# ProProject_TDeck_18650_Charger_2024-02-1.net
KiCad netlist of a schematic drawn in EasyEDA Pro
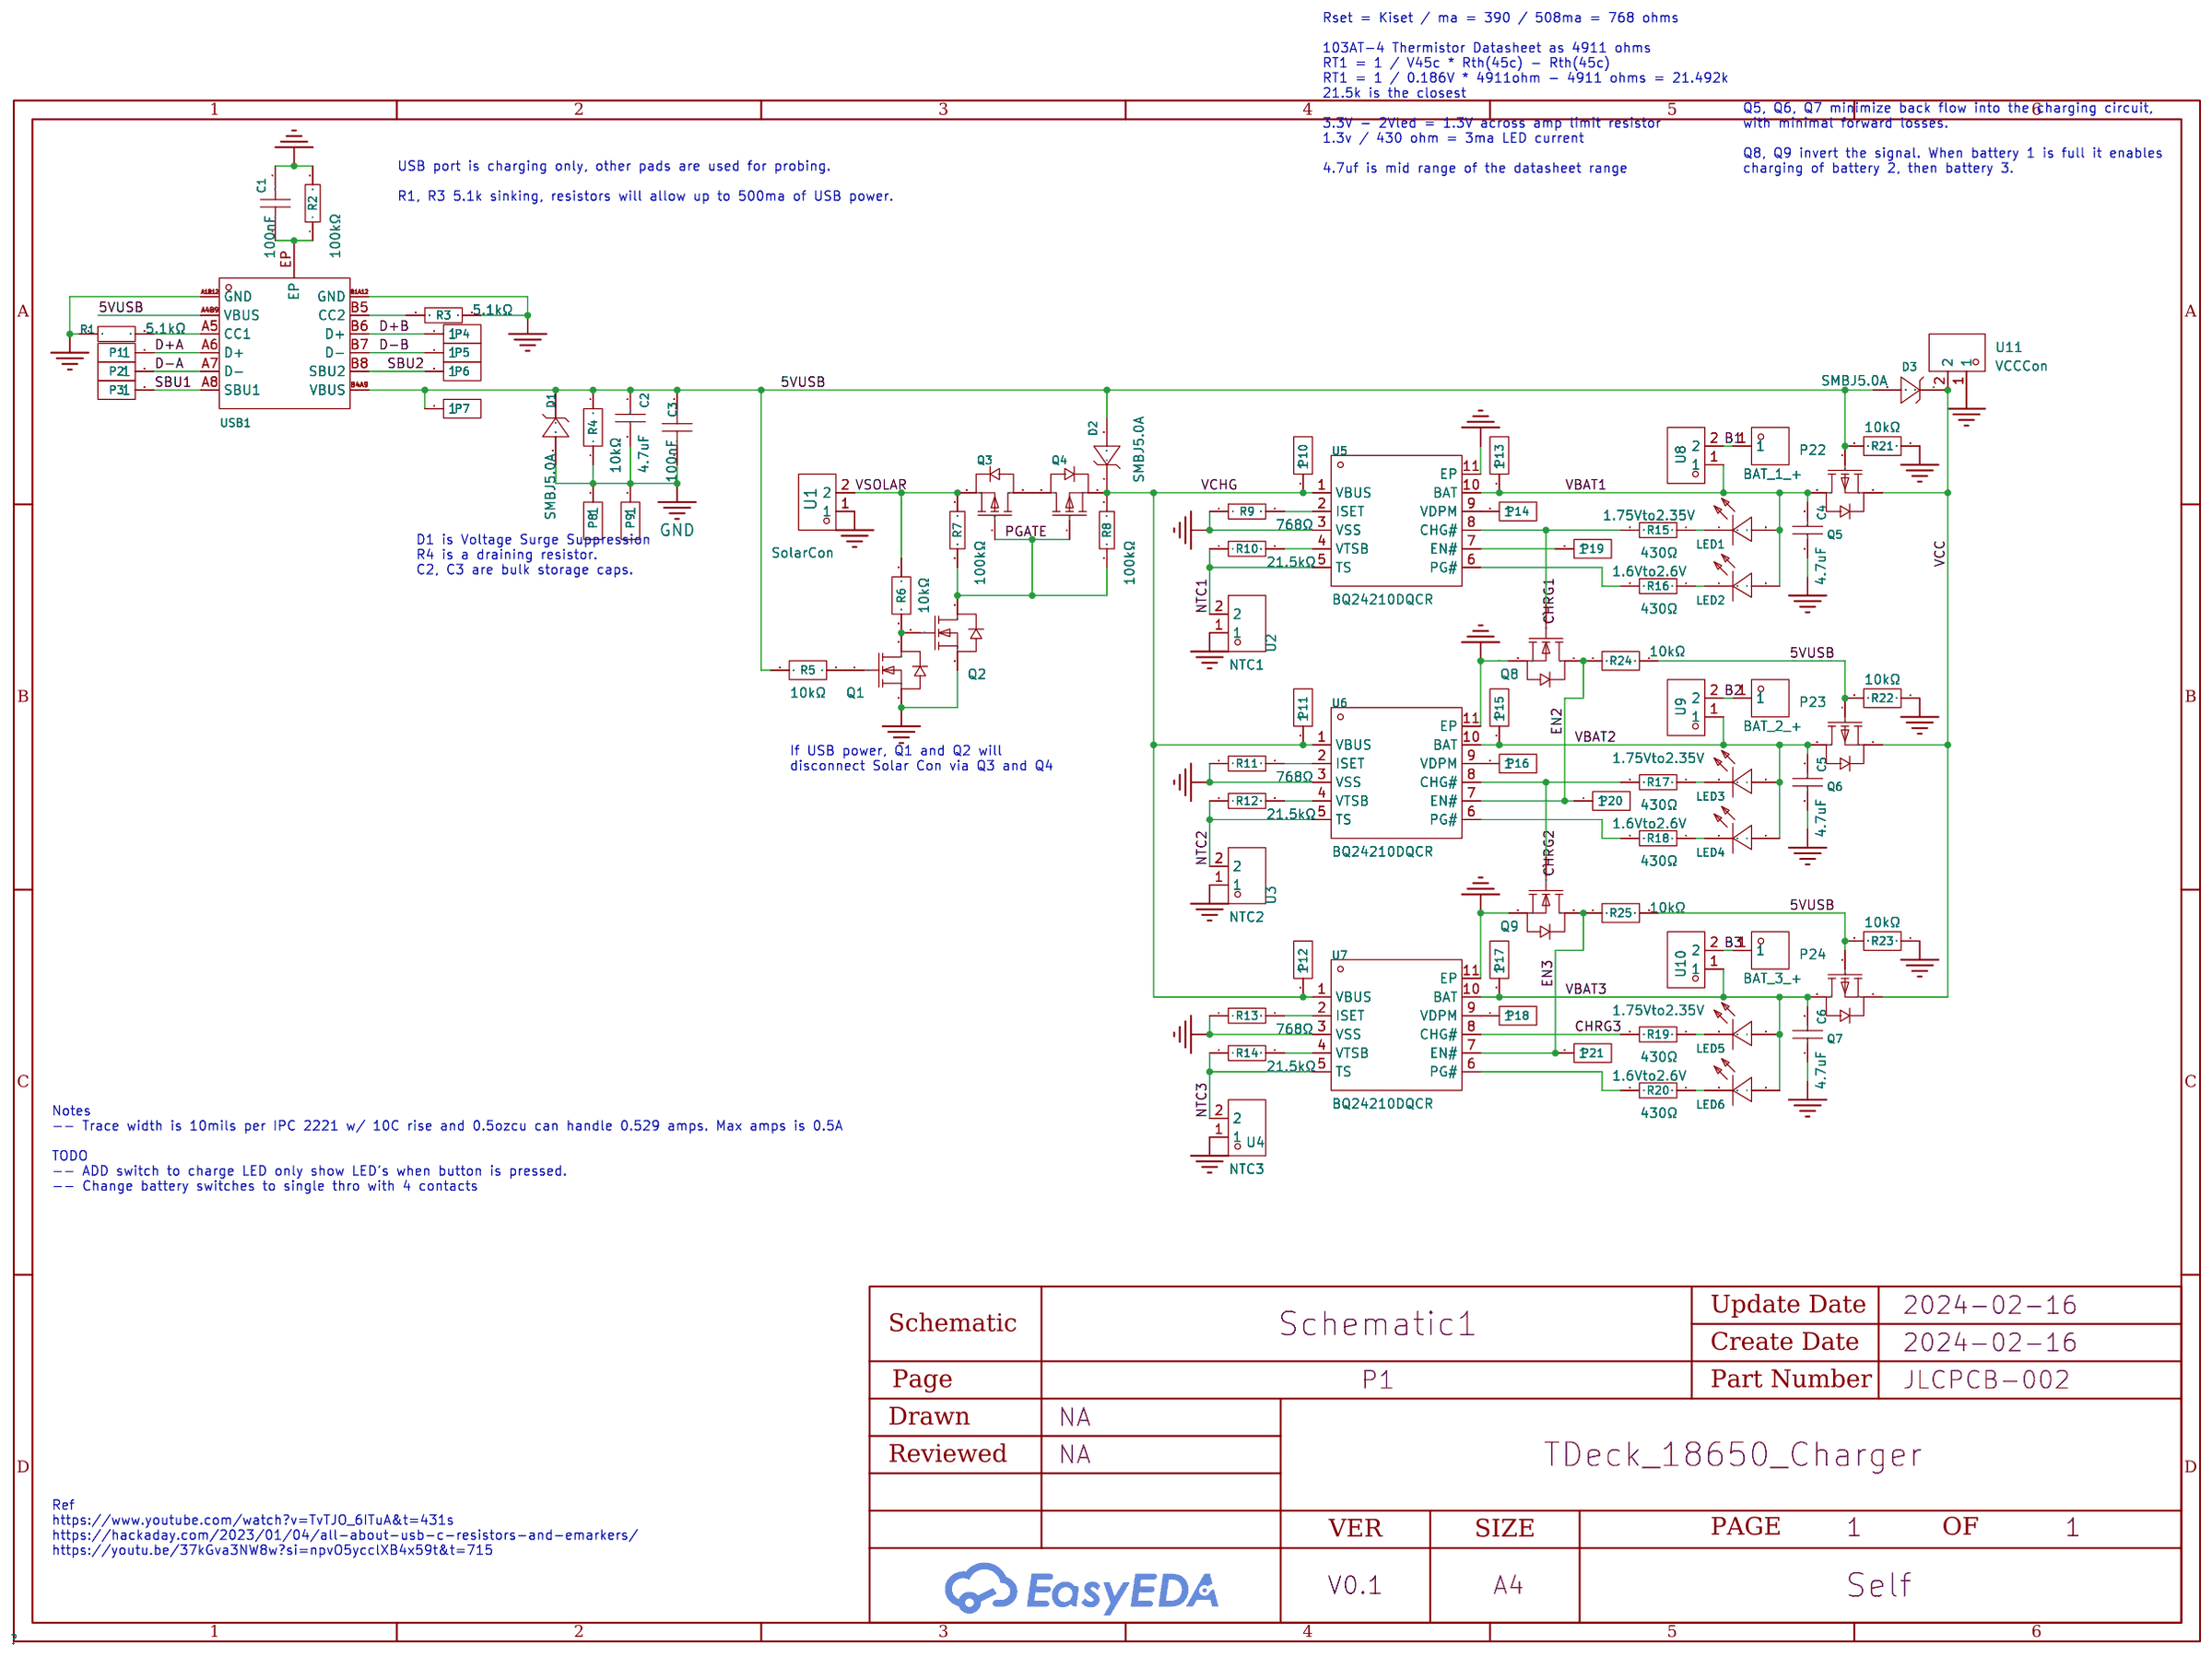
[diagram p0: schematic sheet]

(export (version "E")
  (design (tool "Eeschema 10.0.6"))
  (components
    (comp (ref "C1")
      (value "100nF")
      (footprint "easyedapro:C0603")
      (fields
        (field (name "Manufacturer Part") "CC0603KRX7R9BB104")
        (field (name "Manufacturer") "YAGEO(国巨)")
      )
      (libsource (lib "easyedapro") (part "CC0603KRX7R9BB104"))
    )
    (comp (ref "C2")
      (value "4.7uF")
      (footprint "easyedapro:C1206")
      (fields (field (name "Manufacturer Part") "1206B475K500NT") (field (name "Manufacturer") "FH(风华)"))
      (libsource (lib "easyedapro") (part "1206B475K500NT"))
    )
    (comp (ref "C3")
      (value "100nF")
      (footprint "easyedapro:C0603")
      (fields
        (field (name "Manufacturer Part") "CC0603KRX7R9BB104")
        (field (name "Manufacturer") "YAGEO(国巨)")
      )
      (libsource (lib "easyedapro") (part "CC0603KRX7R9BB104"))
    )
    (comp (ref "C4")
      (value "4.7uF")
      (footprint "easyedapro:C1206")
      (fields (field (name "Manufacturer Part") "1206B475K500NT") (field (name "Manufacturer") "FH(风华)"))
      (libsource (lib "easyedapro") (part "1206B475K500NT"))
    )
    (comp (ref "C5")
      (value "4.7uF")
      (footprint "easyedapro:C1206")
      (fields (field (name "Manufacturer Part") "1206B475K500NT") (field (name "Manufacturer") "FH(风华)"))
      (libsource (lib "easyedapro") (part "1206B475K500NT"))
    )
    (comp (ref "C6")
      (value "4.7uF")
      (footprint "easyedapro:C1206")
      (fields (field (name "Manufacturer Part") "1206B475K500NT") (field (name "Manufacturer") "FH(风华)"))
      (libsource (lib "easyedapro") (part "1206B475K500NT"))
    )
    (comp (ref "D1")
      (value "SMBJ5.0A")
      (footprint "easyedapro:SMB_L4.4-W3.6-LS5.2-RD")
      (fields (field (name "Manufacturer") "PAKER(派克微)"))
      (libsource (lib "easyedapro") (part "SMBJ5.0A_C3012487"))
    )
    (comp (ref "D2")
      (value "SMBJ5.0A")
      (footprint "easyedapro:SMB_L4.4-W3.6-LS5.2-RD")
      (fields (field (name "Manufacturer") "PAKER(派克微)"))
      (libsource (lib "easyedapro") (part "SMBJ5.0A_C3012487"))
    )
    (comp (ref "D3")
      (value "SMBJ5.0A")
      (footprint "easyedapro:SMB_L4.4-W3.6-LS5.2-RD")
      (fields (field (name "Manufacturer") "PAKER(派克微)"))
      (libsource (lib "easyedapro") (part "SMBJ5.0A_C3012487"))
    )
    (comp (ref "LED1")
      (value "1.75Vto2.35V")
      (footprint "easyedapro:LED0805-RD")
      (description "Emitted Color:Red")
      (fields
        (field (name "Manufacturer Part") "BL-HUF35A-AV-TRB")
        (field (name "Manufacturer") "BrtLed(佰鸿)")
      )
      (libsource (lib "easyedapro") (part "17-21/R6C-AQ2R2B/3T"))
    )
    (comp (ref "LED2")
      (value "1.6Vto2.6V")
      (footprint "easyedapro:LED0603-RD")
      (fields (field (name "Manufacturer Part") "NCD0603O2") (field (name "Manufacturer") "国星光电"))
      (libsource (lib "easyedapro") (part "FC-1608YOXK-600H08"))
    )
    (comp (ref "LED3")
      (value "1.75Vto2.35V")
      (footprint "easyedapro:LED0805-RD")
      (description "Emitted Color:Red")
      (fields
        (field (name "Manufacturer Part") "BL-HUF35A-AV-TRB")
        (field (name "Manufacturer") "BrtLed(佰鸿)")
      )
      (libsource (lib "easyedapro") (part "17-21/R6C-AQ2R2B/3T"))
    )
    (comp (ref "LED4")
      (value "1.6Vto2.6V")
      (footprint "easyedapro:LED0603-RD")
      (fields (field (name "Manufacturer Part") "NCD0603O2") (field (name "Manufacturer") "国星光电"))
      (libsource (lib "easyedapro") (part "FC-1608YOXK-600H08"))
    )
    (comp (ref "LED5")
      (value "1.75Vto2.35V")
      (footprint "easyedapro:LED0805-RD")
      (description "Emitted Color:Red")
      (fields
        (field (name "Manufacturer Part") "BL-HUF35A-AV-TRB")
        (field (name "Manufacturer") "BrtLed(佰鸿)")
      )
      (libsource (lib "easyedapro") (part "17-21/R6C-AQ2R2B/3T"))
    )
    (comp (ref "LED6")
      (value "1.6Vto2.6V")
      (footprint "easyedapro:LED0603-RD")
      (fields (field (name "Manufacturer Part") "NCD0603O2") (field (name "Manufacturer") "国星光电"))
      (libsource (lib "easyedapro") (part "FC-1608YOXK-600H08"))
    )
    (comp (ref "P1")
      (value "2.54-1*1P针")
      (footprint "easyedapro:HDR-TH_1P-P2.54-V-M")
      (fields (field (name "Manufacturer") "BOOMELE(博穆精密)"))
      (libsource (lib "easyedapro") (part "Header-Male-2.54_1x1"))
    )
    (comp (ref "P2")
      (value "2.54-1*1P针")
      (footprint "easyedapro:HDR-TH_1P-P2.54-V-M")
      (fields (field (name "Manufacturer") "BOOMELE(博穆精密)"))
      (libsource (lib "easyedapro") (part "Header-Male-2.54_1x1"))
    )
    (comp (ref "P3")
      (value "2.54-1*1P针")
      (footprint "easyedapro:HDR-TH_1P-P2.54-V-M")
      (fields (field (name "Manufacturer") "BOOMELE(博穆精密)"))
      (libsource (lib "easyedapro") (part "Header-Male-2.54_1x1"))
    )
    (comp (ref "P4")
      (value "2.54-1*1P针")
      (footprint "easyedapro:HDR-TH_1P-P2.54-V-M")
      (fields (field (name "Manufacturer") "BOOMELE(博穆精密)"))
      (libsource (lib "easyedapro") (part "Header-Male-2.54_1x1"))
    )
    (comp (ref "P5")
      (value "2.54-1*1P针")
      (footprint "easyedapro:HDR-TH_1P-P2.54-V-M")
      (fields (field (name "Manufacturer") "BOOMELE(博穆精密)"))
      (libsource (lib "easyedapro") (part "Header-Male-2.54_1x1"))
    )
    (comp (ref "P6")
      (value "2.54-1*1P针")
      (footprint "easyedapro:HDR-TH_1P-P2.54-V-M")
      (fields (field (name "Manufacturer") "BOOMELE(博穆精密)"))
      (libsource (lib "easyedapro") (part "Header-Male-2.54_1x1"))
    )
    (comp (ref "P7")
      (value "2.54-1*1P针")
      (footprint "easyedapro:HDR-TH_1P-P2.54-V-M")
      (fields (field (name "Manufacturer") "BOOMELE(博穆精密)"))
      (libsource (lib "easyedapro") (part "Header-Male-2.54_1x1"))
    )
    (comp (ref "P8")
      (value "2.54-1*1P针")
      (footprint "easyedapro:HDR-TH_1P-P2.54-V-M")
      (fields (field (name "Manufacturer") "BOOMELE(博穆精密)"))
      (libsource (lib "easyedapro") (part "Header-Male-2.54_1x1"))
    )
    (comp (ref "P9")
      (value "2.54-1*1P针")
      (footprint "easyedapro:HDR-TH_1P-P2.54-V-M")
      (fields (field (name "Manufacturer") "BOOMELE(博穆精密)"))
      (libsource (lib "easyedapro") (part "Header-Male-2.54_1x1"))
    )
    (comp (ref "P10")
      (value "2.54-1*1P针")
      (footprint "easyedapro:HDR-TH_1P-P2.54-V-M")
      (fields (field (name "Manufacturer") "BOOMELE(博穆精密)"))
      (libsource (lib "easyedapro") (part "Header-Male-2.54_1x1"))
    )
    (comp (ref "P11")
      (value "2.54-1*1P针")
      (footprint "easyedapro:HDR-TH_1P-P2.54-V-M")
      (fields (field (name "Manufacturer") "BOOMELE(博穆精密)"))
      (libsource (lib "easyedapro") (part "Header-Male-2.54_1x1"))
    )
    (comp (ref "P12")
      (value "2.54-1*1P针")
      (footprint "easyedapro:HDR-TH_1P-P2.54-V-M")
      (fields (field (name "Manufacturer") "BOOMELE(博穆精密)"))
      (libsource (lib "easyedapro") (part "Header-Male-2.54_1x1"))
    )
    (comp (ref "P13")
      (value "2.54-1*1P针")
      (footprint "easyedapro:HDR-TH_1P-P2.54-V-M")
      (fields (field (name "Manufacturer") "BOOMELE(博穆精密)"))
      (libsource (lib "easyedapro") (part "Header-Male-2.54_1x1"))
    )
    (comp (ref "P14")
      (value "2.54-1*1P针")
      (footprint "easyedapro:HDR-TH_1P-P2.54-V-M")
      (fields (field (name "Manufacturer") "BOOMELE(博穆精密)"))
      (libsource (lib "easyedapro") (part "Header-Male-2.54_1x1"))
    )
    (comp (ref "P15")
      (value "2.54-1*1P针")
      (footprint "easyedapro:HDR-TH_1P-P2.54-V-M")
      (fields (field (name "Manufacturer") "BOOMELE(博穆精密)"))
      (libsource (lib "easyedapro") (part "Header-Male-2.54_1x1"))
    )
    (comp (ref "P16")
      (value "2.54-1*1P针")
      (footprint "easyedapro:HDR-TH_1P-P2.54-V-M")
      (fields (field (name "Manufacturer") "BOOMELE(博穆精密)"))
      (libsource (lib "easyedapro") (part "Header-Male-2.54_1x1"))
    )
    (comp (ref "P17")
      (value "2.54-1*1P针")
      (footprint "easyedapro:HDR-TH_1P-P2.54-V-M")
      (fields (field (name "Manufacturer") "BOOMELE(博穆精密)"))
      (libsource (lib "easyedapro") (part "Header-Male-2.54_1x1"))
    )
    (comp (ref "P18")
      (value "2.54-1*1P针")
      (footprint "easyedapro:HDR-TH_1P-P2.54-V-M")
      (fields (field (name "Manufacturer") "BOOMELE(博穆精密)"))
      (libsource (lib "easyedapro") (part "Header-Male-2.54_1x1"))
    )
    (comp (ref "P19")
      (value "2.54-1*1P针")
      (footprint "easyedapro:HDR-TH_1P-P2.54-V-M")
      (fields (field (name "Manufacturer") "BOOMELE(博穆精密)"))
      (libsource (lib "easyedapro") (part "Header-Male-2.54_1x1"))
    )
    (comp (ref "P20")
      (value "2.54-1*1P针")
      (footprint "easyedapro:HDR-TH_1P-P2.54-V-M")
      (fields (field (name "Manufacturer") "BOOMELE(博穆精密)"))
      (libsource (lib "easyedapro") (part "Header-Male-2.54_1x1"))
    )
    (comp (ref "P21")
      (value "2.54-1*1P针")
      (footprint "easyedapro:HDR-TH_1P-P2.54-V-M")
      (fields (field (name "Manufacturer") "BOOMELE(博穆精密)"))
      (libsource (lib "easyedapro") (part "Header-Male-2.54_1x1"))
    )
    (comp (ref "P22")
      (value "BAT_1_+")
      (footprint "easyedapro:SMD_BD4.0-L4.0-W4.0-D1.0")
      (fields (field (name "Manufacturer Part") "PAD"))
      (libsource (lib "easyedapro") (part "PAD"))
    )
    (comp (ref "P23")
      (value "BAT_2_+")
      (footprint "easyedapro:SMD_BD4.0-L4.0-W4.0-D1.0")
      (fields (field (name "Manufacturer Part") "PAD"))
      (libsource (lib "easyedapro") (part "PAD"))
    )
    (comp (ref "P24")
      (value "BAT_3_+")
      (footprint "easyedapro:SMD_BD4.0-L4.0-W4.0-D1.0")
      (fields (field (name "Manufacturer Part") "PAD"))
      (libsource (lib "easyedapro") (part "PAD"))
    )
    (comp (ref "Q1")
      (value "AO3400A")
      (footprint "easyedapro:SOT-23-3_L2.9-W1.6-P1.90-LS2.8-BR")
      (fields (field (name "Manufacturer") "AOS"))
      (libsource (lib "easyedapro") (part "AO3400A"))
    )
    (comp (ref "Q2")
      (value "AO3400A")
      (footprint "easyedapro:SOT-23-3_L2.9-W1.6-P1.90-LS2.8-BR")
      (fields (field (name "Manufacturer") "AOS"))
      (libsource (lib "easyedapro") (part "AO3400A"))
    )
    (comp (ref "Q3")
      (value "SI2301")
      (footprint "easyedapro:SOT-23-3_L2.9-W1.3-P1.90-LS2.4-BR")
      (fields (field (name "Manufacturer") "YONGYUTAI(永裕泰)"))
      (libsource (lib "easyedapro") (part "SI2301_C2891731"))
    )
    (comp (ref "Q4")
      (value "SI2301")
      (footprint "easyedapro:SOT-23-3_L2.9-W1.3-P1.90-LS2.4-BR")
      (fields (field (name "Manufacturer") "YONGYUTAI(永裕泰)"))
      (libsource (lib "easyedapro") (part "SI2301_C2891731"))
    )
    (comp (ref "Q5")
      (value "SI2301")
      (footprint "easyedapro:SOT-23-3_L2.9-W1.3-P1.90-LS2.4-BR")
      (fields (field (name "Manufacturer") "YONGYUTAI(永裕泰)"))
      (libsource (lib "easyedapro") (part "SI2301_C2891731"))
    )
    (comp (ref "Q6")
      (value "SI2301")
      (footprint "easyedapro:SOT-23-3_L2.9-W1.3-P1.90-LS2.4-BR")
      (fields (field (name "Manufacturer") "YONGYUTAI(永裕泰)"))
      (libsource (lib "easyedapro") (part "SI2301_C2891731"))
    )
    (comp (ref "Q7")
      (value "SI2301")
      (footprint "easyedapro:SOT-23-3_L2.9-W1.3-P1.90-LS2.4-BR")
      (fields (field (name "Manufacturer") "YONGYUTAI(永裕泰)"))
      (libsource (lib "easyedapro") (part "SI2301_C2891731"))
    )
    (comp (ref "Q8")
      (value "AO3400A")
      (footprint "easyedapro:SOT-23-3_L2.9-W1.6-P1.90-LS2.8-BR")
      (fields (field (name "Manufacturer") "AOS"))
      (libsource (lib "easyedapro") (part "AO3400A"))
    )
    (comp (ref "Q9")
      (value "AO3400A")
      (footprint "easyedapro:SOT-23-3_L2.9-W1.6-P1.90-LS2.8-BR")
      (fields (field (name "Manufacturer") "AOS"))
      (libsource (lib "easyedapro") (part "AO3400A"))
    )
    (comp (ref "R1")
      (value "5.1kΩ")
      (footprint "easyedapro:R0805")
      (fields
        (field (name "Manufacturer Part") "0805W8F5101T5E")
        (field (name "Manufacturer") "UNI-ROYAL(厚声)")
      )
      (libsource (lib "easyedapro") (part "0805W8F5101T5E"))
    )
    (comp (ref "R2")
      (value "100kΩ")
      (footprint "easyedapro:R0805")
      (fields
        (field (name "Manufacturer Part") "0805W8F1003T5E")
        (field (name "Manufacturer") "UNI-ROYAL(厚声)")
      )
      (libsource (lib "easyedapro") (part "0805W8F1003T5E_C149504"))
    )
    (comp (ref "R3")
      (value "5.1kΩ")
      (footprint "easyedapro:R0805")
      (fields
        (field (name "Manufacturer Part") "0805W8F5101T5E")
        (field (name "Manufacturer") "UNI-ROYAL(厚声)")
      )
      (libsource (lib "easyedapro") (part "0805W8F5101T5E"))
    )
    (comp (ref "R4")
      (value "10kΩ")
      (footprint "easyedapro:R0805")
      (fields (field (name "Manufacturer Part") "AR05DTD1002") (field (name "Manufacturer") "Viking(光颉)"))
      (libsource (lib "easyedapro") (part "AR05DTD1002"))
    )
    (comp (ref "R5")
      (value "10kΩ")
      (footprint "easyedapro:R0805")
      (fields (field (name "Manufacturer Part") "AR05DTD1002") (field (name "Manufacturer") "Viking(光颉)"))
      (libsource (lib "easyedapro") (part "AR05DTD1002"))
    )
    (comp (ref "R6")
      (value "10kΩ")
      (footprint "easyedapro:R0805")
      (fields (field (name "Manufacturer Part") "AR05DTD1002") (field (name "Manufacturer") "Viking(光颉)"))
      (libsource (lib "easyedapro") (part "AR05DTD1002"))
    )
    (comp (ref "R7")
      (value "100kΩ")
      (footprint "easyedapro:R0805")
      (fields
        (field (name "Manufacturer Part") "0805W8F1003T5E")
        (field (name "Manufacturer") "UNI-ROYAL(厚声)")
      )
      (libsource (lib "easyedapro") (part "0805W8F1003T5E_C149504"))
    )
    (comp (ref "R8")
      (value "100kΩ")
      (footprint "easyedapro:R0805")
      (fields
        (field (name "Manufacturer Part") "0805W8F1003T5E")
        (field (name "Manufacturer") "UNI-ROYAL(厚声)")
      )
      (libsource (lib "easyedapro") (part "0805W8F1003T5E_C149504"))
    )
    (comp (ref "R9")
      (value "768Ω")
      (footprint "easyedapro:R0805")
      (fields (field (name "Manufacturer Part") "AC0805FR-07768RL") (field (name "Manufacturer") "YAGEO(国巨)"))
      (libsource (lib "easyedapro") (part "AC0805FR-07768RL"))
    )
    (comp (ref "R10")
      (value "21.5kΩ")
      (footprint "easyedapro:R0805")
      (fields (field (name "Manufacturer Part") "CR0805-FX-2152ELF") (field (name "Manufacturer") "BOURNS"))
      (libsource (lib "easyedapro") (part "CR0805-FX-2152ELF"))
    )
    (comp (ref "R11")
      (value "768Ω")
      (footprint "easyedapro:R0805")
      (fields (field (name "Manufacturer Part") "AC0805FR-07768RL") (field (name "Manufacturer") "YAGEO(国巨)"))
      (libsource (lib "easyedapro") (part "AC0805FR-07768RL"))
    )
    (comp (ref "R12")
      (value "21.5kΩ")
      (footprint "easyedapro:R0805")
      (fields (field (name "Manufacturer Part") "CR0805-FX-2152ELF") (field (name "Manufacturer") "BOURNS"))
      (libsource (lib "easyedapro") (part "CR0805-FX-2152ELF"))
    )
    (comp (ref "R13")
      (value "768Ω")
      (footprint "easyedapro:R0805")
      (fields (field (name "Manufacturer Part") "AC0805FR-07768RL") (field (name "Manufacturer") "YAGEO(国巨)"))
      (libsource (lib "easyedapro") (part "AC0805FR-07768RL"))
    )
    (comp (ref "R14")
      (value "21.5kΩ")
      (footprint "easyedapro:R0805")
      (fields (field (name "Manufacturer Part") "CR0805-FX-2152ELF") (field (name "Manufacturer") "BOURNS"))
      (libsource (lib "easyedapro") (part "CR0805-FX-2152ELF"))
    )
    (comp (ref "R15")
      (value "430Ω")
      (footprint "easyedapro:R0603")
      (fields
        (field (name "Manufacturer Part") "0603WAF4300T5E")
        (field (name "Manufacturer") "UNI-ROYAL(厚声)")
      )
      (libsource (lib "easyedapro") (part "0603WAF4300T5E"))
    )
    (comp (ref "R16")
      (value "430Ω")
      (footprint "easyedapro:R0603")
      (fields
        (field (name "Manufacturer Part") "0603WAF4300T5E")
        (field (name "Manufacturer") "UNI-ROYAL(厚声)")
      )
      (libsource (lib "easyedapro") (part "0603WAF4300T5E"))
    )
    (comp (ref "R17")
      (value "430Ω")
      (footprint "easyedapro:R0603")
      (fields
        (field (name "Manufacturer Part") "0603WAF4300T5E")
        (field (name "Manufacturer") "UNI-ROYAL(厚声)")
      )
      (libsource (lib "easyedapro") (part "0603WAF4300T5E"))
    )
    (comp (ref "R18")
      (value "430Ω")
      (footprint "easyedapro:R0603")
      (fields
        (field (name "Manufacturer Part") "0603WAF4300T5E")
        (field (name "Manufacturer") "UNI-ROYAL(厚声)")
      )
      (libsource (lib "easyedapro") (part "0603WAF4300T5E"))
    )
    (comp (ref "R19")
      (value "430Ω")
      (footprint "easyedapro:R0603")
      (fields
        (field (name "Manufacturer Part") "0603WAF4300T5E")
        (field (name "Manufacturer") "UNI-ROYAL(厚声)")
      )
      (libsource (lib "easyedapro") (part "0603WAF4300T5E"))
    )
    (comp (ref "R20")
      (value "430Ω")
      (footprint "easyedapro:R0603")
      (fields
        (field (name "Manufacturer Part") "0603WAF4300T5E")
        (field (name "Manufacturer") "UNI-ROYAL(厚声)")
      )
      (libsource (lib "easyedapro") (part "0603WAF4300T5E"))
    )
    (comp (ref "R21")
      (value "10kΩ")
      (footprint "easyedapro:R0805")
      (fields (field (name "Manufacturer Part") "AR05DTD1002") (field (name "Manufacturer") "Viking(光颉)"))
      (libsource (lib "easyedapro") (part "AR05DTD1002"))
    )
    (comp (ref "R22")
      (value "10kΩ")
      (footprint "easyedapro:R0805")
      (fields (field (name "Manufacturer Part") "AR05DTD1002") (field (name "Manufacturer") "Viking(光颉)"))
      (libsource (lib "easyedapro") (part "AR05DTD1002"))
    )
    (comp (ref "R23")
      (value "10kΩ")
      (footprint "easyedapro:R0805")
      (fields (field (name "Manufacturer Part") "AR05DTD1002") (field (name "Manufacturer") "Viking(光颉)"))
      (libsource (lib "easyedapro") (part "AR05DTD1002"))
    )
    (comp (ref "R24")
      (value "10kΩ")
      (footprint "easyedapro:R0805")
      (fields (field (name "Manufacturer Part") "AR05DTD1002") (field (name "Manufacturer") "Viking(光颉)"))
      (libsource (lib "easyedapro") (part "AR05DTD1002"))
    )
    (comp (ref "R25")
      (value "10kΩ")
      (footprint "easyedapro:R0805")
      (fields (field (name "Manufacturer Part") "AR05DTD1002") (field (name "Manufacturer") "Viking(光颉)"))
      (libsource (lib "easyedapro") (part "AR05DTD1002"))
    )
    (comp (ref "U1")
      (value "SolarCon")
      (footprint "easyedapro:CONN-TH_XY308-2.54-2P")
      (fields
        (field (name "Manufacturer Part") "XY308-2.54-2P")
        (field (name "Manufacturer") "XINLAIYA(新莱亚)")
      )
      (libsource (lib "easyedapro") (part "XY308-2.54-2P"))
    )
    (comp (ref "U2")
      (value "NTC1")
      (footprint "easyedapro:HDR-TH_2P-P2.54-V-M-2")
      (fields
        (field (name "Manufacturer Part") "5-146472-2")
        (field (name "Manufacturer") "TE Connectivity(泰科电子)")
      )
      (libsource (lib "easyedapro") (part "5-146472-2"))
    )
    (comp (ref "U3")
      (value "NTC2")
      (footprint "easyedapro:HDR-TH_2P-P2.54-V-M-2")
      (fields
        (field (name "Manufacturer Part") "5-146472-2")
        (field (name "Manufacturer") "TE Connectivity(泰科电子)")
      )
      (libsource (lib "easyedapro") (part "5-146472-2"))
    )
    (comp (ref "U4")
      (value "NTC3")
      (footprint "easyedapro:HDR-TH_2P-P2.54-V-M-2")
      (fields
        (field (name "Manufacturer Part") "5-146472-2")
        (field (name "Manufacturer") "TE Connectivity(泰科电子)")
      )
      (libsource (lib "easyedapro") (part "5-146472-2"))
    )
    (comp (ref "U5")
      (value "BQ24210DQCR")
      (footprint "easyedapro:WSON-10_L3.0-W2.0-P0.50-BL-EP")
      (fields (field (name "Manufacturer") "TI(德州仪器)"))
      (libsource (lib "easyedapro") (part "BQ24210DQCR"))
    )
    (comp (ref "U6")
      (value "BQ24210DQCR")
      (footprint "easyedapro:WSON-10_L3.0-W2.0-P0.50-BL-EP")
      (fields (field (name "Manufacturer") "TI(德州仪器)"))
      (libsource (lib "easyedapro") (part "BQ24210DQCR"))
    )
    (comp (ref "U7")
      (value "BQ24210DQCR")
      (footprint "easyedapro:WSON-10_L3.0-W2.0-P0.50-BL-EP")
      (fields (field (name "Manufacturer") "TI(德州仪器)"))
      (libsource (lib "easyedapro") (part "BQ24210DQCR"))
    )
    (comp (ref "U8")
      (value "DIS-CON-SW")
      (footprint "easyedapro:HDR-TH_2P-P2.54-V-M-2")
      (fields
        (field (name "Manufacturer Part") "5-146472-2")
        (field (name "Manufacturer") "TE Connectivity(泰科电子)")
      )
      (libsource (lib "easyedapro") (part "5-146472-2"))
    )
    (comp (ref "U9")
      (value "DIS-CON-SW")
      (footprint "easyedapro:HDR-TH_2P-P2.54-V-M-2")
      (fields
        (field (name "Manufacturer Part") "5-146472-2")
        (field (name "Manufacturer") "TE Connectivity(泰科电子)")
      )
      (libsource (lib "easyedapro") (part "5-146472-2"))
    )
    (comp (ref "U10")
      (value "DIS-CON-SW")
      (footprint "easyedapro:HDR-TH_2P-P2.54-V-M-2")
      (fields
        (field (name "Manufacturer Part") "5-146472-2")
        (field (name "Manufacturer") "TE Connectivity(泰科电子)")
      )
      (libsource (lib "easyedapro") (part "5-146472-2"))
    )
    (comp (ref "U11")
      (value "VCCCon")
      (footprint "easyedapro:HDR-TH_2P-P2.54-V-M-2")
      (fields
        (field (name "Manufacturer Part") "5-146472-2")
        (field (name "Manufacturer") "TE Connectivity(泰科电子)")
      )
      (libsource (lib "easyedapro") (part "5-146472-2"))
    )
    (comp (ref "USB1")
      (value "TYPEC-304-ACP16")
      (footprint "easyedapro:USB-C-SMD_TYPE-C-16P-1")
      (fields (field (name "Manufacturer") "XUNPU(讯普)"))
      (libsource (lib "easyedapro") (part "TYPEC-304-ACP16"))
    )
  )
  (nets
    (net (code "1") (name "/5VUSB") (class "Default")
      (node (ref "C2") (pin "2") (pinfunction "2_2") (pintype "input"))
      (node (ref "C3") (pin "2") (pinfunction "2_2") (pintype "input"))
      (node (ref "D1") (pin "1") (pinfunction "1_1") (pintype "input"))
      (node (ref "D2") (pin "2") (pinfunction "2_2") (pintype "input"))
      (node (ref "D3") (pin "2") (pinfunction "2_2") (pintype "input"))
      (node (ref "P7") (pin "1") (pinfunction "1_1") (pintype "input"))
      (node (ref "Q5") (pin "1") (pinfunction "G_1") (pintype "input"))
      (node (ref "Q6") (pin "1") (pinfunction "G_1") (pintype "input"))
      (node (ref "Q7") (pin "1") (pinfunction "G_1") (pintype "input"))
      (node (ref "R21") (pin "2") (pinfunction "2_2") (pintype "input"))
      (node (ref "R22") (pin "2") (pinfunction "2_2") (pintype "input"))
      (node (ref "R23") (pin "2") (pinfunction "2_2") (pintype "input"))
      (node (ref "R24") (pin "2") (pinfunction "2_2") (pintype "input"))
      (node (ref "R25") (pin "2") (pinfunction "2_2") (pintype "input"))
      (node (ref "R4") (pin "2") (pinfunction "2_2") (pintype "input"))
      (node (ref "R5") (pin "2") (pinfunction "2_2") (pintype "input"))
      (node (ref "USB1") (pin "A4B9") (pinfunction "VBUS_A4B9") (pintype "input"))
      (node (ref "USB1") (pin "B4A9") (pinfunction "VBUS_B4A9") (pintype "input"))
    )
    (net (code "2") (name "/B1") (class "Default")
      (node (ref "P22") (pin "1") (pinfunction "1_1") (pintype "input"))
      (node (ref "U8") (pin "2") (pinfunction "2_2") (pintype "unspecified"))
    )
    (net (code "3") (name "/B2") (class "Default")
      (node (ref "P23") (pin "1") (pinfunction "1_1") (pintype "input"))
      (node (ref "U9") (pin "2") (pinfunction "2_2") (pintype "unspecified"))
    )
    (net (code "4") (name "/B3") (class "Default")
      (node (ref "P24") (pin "1") (pinfunction "1_1") (pintype "input"))
      (node (ref "U10") (pin "2") (pinfunction "2_2") (pintype "unspecified"))
    )
    (net (code "5") (name "/CHRG1") (class "Default")
      (node (ref "Q8") (pin "1") (pinfunction "G_1") (pintype "input"))
      (node (ref "R15") (pin "2") (pinfunction "2_2") (pintype "input"))
      (node (ref "U5") (pin "8") (pinfunction "CHG#_8") (pintype "input"))
    )
    (net (code "6") (name "/CHRG2") (class "Default")
      (node (ref "Q9") (pin "1") (pinfunction "G_1") (pintype "input"))
      (node (ref "R17") (pin "2") (pinfunction "2_2") (pintype "input"))
      (node (ref "U6") (pin "8") (pinfunction "CHG#_8") (pintype "input"))
    )
    (net (code "7") (name "/CHRG3") (class "Default")
      (node (ref "R19") (pin "2") (pinfunction "2_2") (pintype "input"))
      (node (ref "U7") (pin "8") (pinfunction "CHG#_8") (pintype "input"))
    )
    (net (code "8") (name "/D+A") (class "Default")
      (node (ref "P1") (pin "1") (pinfunction "1_1") (pintype "input"))
      (node (ref "USB1") (pin "A6") (pinfunction "D+_A6") (pintype "input"))
    )
    (net (code "9") (name "/D+B") (class "Default")
      (node (ref "P4") (pin "1") (pinfunction "1_1") (pintype "input"))
      (node (ref "USB1") (pin "B6") (pinfunction "D+_B6") (pintype "input"))
    )
    (net (code "10") (name "/D-A") (class "Default")
      (node (ref "P2") (pin "1") (pinfunction "1_1") (pintype "input"))
      (node (ref "USB1") (pin "A7") (pinfunction "D-_A7") (pintype "input"))
    )
    (net (code "11") (name "/D-B") (class "Default")
      (node (ref "P5") (pin "1") (pinfunction "1_1") (pintype "input"))
      (node (ref "USB1") (pin "B7") (pinfunction "D-_B7") (pintype "input"))
    )
    (net (code "12") (name "/EN2") (class "Default")
      (node (ref "P20") (pin "1") (pinfunction "1_1") (pintype "input"))
      (node (ref "Q8") (pin "3") (pinfunction "D_3") (pintype "input"))
      (node (ref "R24") (pin "1") (pinfunction "1_1") (pintype "input"))
      (node (ref "U6") (pin "7") (pinfunction "EN#_7") (pintype "input"))
    )
    (net (code "13") (name "/EN3") (class "Default")
      (node (ref "P21") (pin "1") (pinfunction "1_1") (pintype "input"))
      (node (ref "Q9") (pin "3") (pinfunction "D_3") (pintype "input"))
      (node (ref "R25") (pin "1") (pinfunction "1_1") (pintype "input"))
      (node (ref "U7") (pin "7") (pinfunction "EN#_7") (pintype "input"))
    )
    (net (code "14") (name "/NTC1") (class "Default")
      (node (ref "R10") (pin "1") (pinfunction "1_1") (pintype "input"))
      (node (ref "U2") (pin "2") (pinfunction "2_2") (pintype "unspecified"))
      (node (ref "U5") (pin "5") (pinfunction "TS_5") (pintype "input"))
    )
    (net (code "15") (name "/NTC2") (class "Default")
      (node (ref "R12") (pin "1") (pinfunction "1_1") (pintype "input"))
      (node (ref "U3") (pin "2") (pinfunction "2_2") (pintype "unspecified"))
      (node (ref "U6") (pin "5") (pinfunction "TS_5") (pintype "input"))
    )
    (net (code "16") (name "/NTC3") (class "Default")
      (node (ref "R14") (pin "1") (pinfunction "1_1") (pintype "input"))
      (node (ref "U4") (pin "2") (pinfunction "2_2") (pintype "unspecified"))
      (node (ref "U7") (pin "5") (pinfunction "TS_5") (pintype "input"))
    )
    (net (code "17") (name "/PGATE") (class "Default")
      (node (ref "Q2") (pin "3") (pinfunction "D_3") (pintype "input"))
      (node (ref "Q3") (pin "1") (pinfunction "G_1") (pintype "input"))
      (node (ref "Q4") (pin "1") (pinfunction "G_1") (pintype "input"))
      (node (ref "R7") (pin "1") (pinfunction "1_1") (pintype "input"))
      (node (ref "R8") (pin "1") (pinfunction "1_1") (pintype "input"))
    )
    (net (code "18") (name "/SBU1") (class "Default")
      (node (ref "P3") (pin "1") (pinfunction "1_1") (pintype "input"))
      (node (ref "USB1") (pin "A8") (pinfunction "SBU1_A8") (pintype "input"))
    )
    (net (code "19") (name "/SBU2") (class "Default")
      (node (ref "P6") (pin "1") (pinfunction "1_1") (pintype "input"))
      (node (ref "USB1") (pin "B8") (pinfunction "SBU2_B8") (pintype "input"))
    )
    (net (code "20") (name "/VBAT1") (class "Default")
      (node (ref "C4") (pin "2") (pinfunction "2_2") (pintype "input"))
      (node (ref "LED1") (pin "2") (pinfunction "A_2") (pintype "input"))
      (node (ref "LED2") (pin "2") (pinfunction "A_2") (pintype "input"))
      (node (ref "P13") (pin "1") (pinfunction "1_1") (pintype "input"))
      (node (ref "Q5") (pin "3") (pinfunction "D_3") (pintype "input"))
      (node (ref "U5") (pin "10") (pinfunction "BAT_10") (pintype "input"))
      (node (ref "U8") (pin "1") (pinfunction "1_1") (pintype "unspecified"))
    )
    (net (code "21") (name "/VBAT2") (class "Default")
      (node (ref "C5") (pin "2") (pinfunction "2_2") (pintype "input"))
      (node (ref "LED3") (pin "2") (pinfunction "A_2") (pintype "input"))
      (node (ref "LED4") (pin "2") (pinfunction "A_2") (pintype "input"))
      (node (ref "P15") (pin "1") (pinfunction "1_1") (pintype "input"))
      (node (ref "Q6") (pin "3") (pinfunction "D_3") (pintype "input"))
      (node (ref "U6") (pin "10") (pinfunction "BAT_10") (pintype "input"))
      (node (ref "U9") (pin "1") (pinfunction "1_1") (pintype "unspecified"))
    )
    (net (code "22") (name "/VBAT3") (class "Default")
      (node (ref "C6") (pin "2") (pinfunction "2_2") (pintype "input"))
      (node (ref "LED5") (pin "2") (pinfunction "A_2") (pintype "input"))
      (node (ref "LED6") (pin "2") (pinfunction "A_2") (pintype "input"))
      (node (ref "P17") (pin "1") (pinfunction "1_1") (pintype "input"))
      (node (ref "Q7") (pin "3") (pinfunction "D_3") (pintype "input"))
      (node (ref "U10") (pin "1") (pinfunction "1_1") (pintype "unspecified"))
      (node (ref "U7") (pin "10") (pinfunction "BAT_10") (pintype "input"))
    )
    (net (code "23") (name "/VCC") (class "Default")
      (node (ref "D3") (pin "1") (pinfunction "1_1") (pintype "input"))
      (node (ref "Q5") (pin "2") (pinfunction "S_2") (pintype "input"))
      (node (ref "Q6") (pin "2") (pinfunction "S_2") (pintype "input"))
      (node (ref "Q7") (pin "2") (pinfunction "S_2") (pintype "input"))
      (node (ref "U11") (pin "2") (pinfunction "2_2") (pintype "unspecified"))
    )
    (net (code "24") (name "/VCHG") (class "Default")
      (node (ref "D2") (pin "1") (pinfunction "1_1") (pintype "input"))
      (node (ref "P10") (pin "1") (pinfunction "1_1") (pintype "input"))
      (node (ref "P11") (pin "1") (pinfunction "1_1") (pintype "input"))
      (node (ref "P12") (pin "1") (pinfunction "1_1") (pintype "input"))
      (node (ref "Q4") (pin "2") (pinfunction "S_2") (pintype "input"))
      (node (ref "R8") (pin "2") (pinfunction "2_2") (pintype "input"))
      (node (ref "U5") (pin "1") (pinfunction "VBUS_1") (pintype "input"))
      (node (ref "U6") (pin "1") (pinfunction "VBUS_1") (pintype "input"))
      (node (ref "U7") (pin "1") (pinfunction "VBUS_1") (pintype "input"))
    )
    (net (code "25") (name "/VSOLAR") (class "Default")
      (node (ref "Q3") (pin "2") (pinfunction "S_2") (pintype "input"))
      (node (ref "R6") (pin "2") (pinfunction "2_2") (pintype "input"))
      (node (ref "R7") (pin "2") (pinfunction "2_2") (pintype "input"))
      (node (ref "U1") (pin "2") (pinfunction "2_2") (pintype "input"))
    )
    (net (code "26") (name "GND") (class "Default")
      (node (ref "C1") (pin "2") (pinfunction "2_2") (pintype "input"))
      (node (ref "C2") (pin "1") (pinfunction "1_1") (pintype "input"))
      (node (ref "C3") (pin "1") (pinfunction "1_1") (pintype "input"))
      (node (ref "C4") (pin "1") (pinfunction "1_1") (pintype "input"))
      (node (ref "C5") (pin "1") (pinfunction "1_1") (pintype "input"))
      (node (ref "C6") (pin "1") (pinfunction "1_1") (pintype "input"))
      (node (ref "D1") (pin "2") (pinfunction "2_2") (pintype "input"))
      (node (ref "P8") (pin "1") (pinfunction "1_1") (pintype "input"))
      (node (ref "P9") (pin "1") (pinfunction "1_1") (pintype "input"))
      (node (ref "Q1") (pin "2") (pinfunction "S_2") (pintype "input"))
      (node (ref "Q2") (pin "2") (pinfunction "S_2") (pintype "input"))
      (node (ref "Q8") (pin "2") (pinfunction "S_2") (pintype "input"))
      (node (ref "Q9") (pin "2") (pinfunction "S_2") (pintype "input"))
      (node (ref "R1") (pin "1") (pinfunction "1_1") (pintype "input"))
      (node (ref "R11") (pin "1") (pinfunction "1_1") (pintype "unspecified"))
      (node (ref "R13") (pin "1") (pinfunction "1_1") (pintype "unspecified"))
      (node (ref "R2") (pin "2") (pinfunction "2_2") (pintype "input"))
      (node (ref "R21") (pin "1") (pinfunction "1_1") (pintype "input"))
      (node (ref "R22") (pin "1") (pinfunction "1_1") (pintype "input"))
      (node (ref "R23") (pin "1") (pinfunction "1_1") (pintype "input"))
      (node (ref "R3") (pin "2") (pinfunction "2_2") (pintype "input"))
      (node (ref "R4") (pin "1") (pinfunction "1_1") (pintype "input"))
      (node (ref "R9") (pin "1") (pinfunction "1_1") (pintype "unspecified"))
      (node (ref "U1") (pin "1") (pinfunction "1_1") (pintype "input"))
      (node (ref "U11") (pin "1") (pinfunction "1_1") (pintype "unspecified"))
      (node (ref "U2") (pin "1") (pinfunction "1_1") (pintype "unspecified"))
      (node (ref "U3") (pin "1") (pinfunction "1_1") (pintype "unspecified"))
      (node (ref "U4") (pin "1") (pinfunction "1_1") (pintype "unspecified"))
      (node (ref "U5") (pin "11") (pinfunction "EP_11") (pintype "input"))
      (node (ref "U5") (pin "3") (pinfunction "VSS_3") (pintype "input"))
      (node (ref "U6") (pin "11") (pinfunction "EP_11") (pintype "input"))
      (node (ref "U6") (pin "3") (pinfunction "VSS_3") (pintype "input"))
      (node (ref "U7") (pin "11") (pinfunction "EP_11") (pintype "input"))
      (node (ref "U7") (pin "3") (pinfunction "VSS_3") (pintype "input"))
      (node (ref "USB1") (pin "A1B12") (pinfunction "GND_A1B12") (pintype "input"))
      (node (ref "USB1") (pin "B1A12") (pinfunction "GND_B1A12") (pintype "input"))
    )
    (net (code "27") (name "Net-(C1-Pad1)") (class "Default")
      (node (ref "C1") (pin "1") (pinfunction "1_1") (pintype "input"))
      (node (ref "R2") (pin "1") (pinfunction "1_1") (pintype "input"))
      (node (ref "USB1") (pin "EP") (pinfunction "EP_EP") (pintype "input"))
    )
    (net (code "28") (name "Net-(LED1-K)") (class "Default")
      (node (ref "LED1") (pin "1") (pinfunction "K_1") (pintype "input"))
      (node (ref "R15") (pin "1") (pinfunction "1_1") (pintype "input"))
    )
    (net (code "29") (name "Net-(LED2-K)") (class "Default")
      (node (ref "LED2") (pin "1") (pinfunction "K_1") (pintype "input"))
      (node (ref "R16") (pin "1") (pinfunction "1_1") (pintype "input"))
    )
    (net (code "30") (name "Net-(LED3-K)") (class "Default")
      (node (ref "LED3") (pin "1") (pinfunction "K_1") (pintype "input"))
      (node (ref "R17") (pin "1") (pinfunction "1_1") (pintype "input"))
    )
    (net (code "31") (name "Net-(LED4-K)") (class "Default")
      (node (ref "LED4") (pin "1") (pinfunction "K_1") (pintype "input"))
      (node (ref "R18") (pin "1") (pinfunction "1_1") (pintype "input"))
    )
    (net (code "32") (name "Net-(LED5-K)") (class "Default")
      (node (ref "LED5") (pin "1") (pinfunction "K_1") (pintype "input"))
      (node (ref "R19") (pin "1") (pinfunction "1_1") (pintype "input"))
    )
    (net (code "33") (name "Net-(LED6-K)") (class "Default")
      (node (ref "LED6") (pin "1") (pinfunction "K_1") (pintype "input"))
      (node (ref "R20") (pin "1") (pinfunction "1_1") (pintype "input"))
    )
    (net (code "34") (name "Net-(Q1-D)") (class "Default")
      (node (ref "Q1") (pin "3") (pinfunction "D_3") (pintype "input"))
      (node (ref "Q2") (pin "1") (pinfunction "G_1") (pintype "input"))
      (node (ref "R6") (pin "1") (pinfunction "1_1") (pintype "input"))
    )
    (net (code "35") (name "Net-(Q1-G)") (class "Default")
      (node (ref "Q1") (pin "1") (pinfunction "G_1") (pintype "input"))
      (node (ref "R5") (pin "1") (pinfunction "1_1") (pintype "input"))
    )
    (net (code "36") (name "Net-(Q3-D)") (class "Default")
      (node (ref "Q3") (pin "3") (pinfunction "D_3") (pintype "input"))
      (node (ref "Q4") (pin "3") (pinfunction "D_3") (pintype "input"))
    )
    (net (code "37") (name "Net-(U5-EN#)") (class "Default")
      (node (ref "P19") (pin "1") (pinfunction "1_1") (pintype "input"))
      (node (ref "U5") (pin "7") (pinfunction "EN#_7") (pintype "input"))
    )
    (net (code "38") (name "Net-(U5-ISET)") (class "Default")
      (node (ref "R9") (pin "2") (pinfunction "2_2") (pintype "unspecified"))
      (node (ref "U5") (pin "2") (pinfunction "ISET_2") (pintype "input"))
    )
    (net (code "39") (name "Net-(U5-PG#)") (class "Default")
      (node (ref "R16") (pin "2") (pinfunction "2_2") (pintype "input"))
      (node (ref "U5") (pin "6") (pinfunction "PG#_6") (pintype "input"))
    )
    (net (code "40") (name "Net-(U5-VDPM)") (class "Default")
      (node (ref "P14") (pin "1") (pinfunction "1_1") (pintype "input"))
      (node (ref "U5") (pin "9") (pinfunction "VDPM_9") (pintype "input"))
    )
    (net (code "41") (name "Net-(U5-VTSB)") (class "Default")
      (node (ref "R10") (pin "2") (pinfunction "2_2") (pintype "input"))
      (node (ref "U5") (pin "4") (pinfunction "VTSB_4") (pintype "input"))
    )
    (net (code "42") (name "Net-(U6-ISET)") (class "Default")
      (node (ref "R11") (pin "2") (pinfunction "2_2") (pintype "unspecified"))
      (node (ref "U6") (pin "2") (pinfunction "ISET_2") (pintype "input"))
    )
    (net (code "43") (name "Net-(U6-PG#)") (class "Default")
      (node (ref "R18") (pin "2") (pinfunction "2_2") (pintype "input"))
      (node (ref "U6") (pin "6") (pinfunction "PG#_6") (pintype "input"))
    )
    (net (code "44") (name "Net-(U6-VDPM)") (class "Default")
      (node (ref "P16") (pin "1") (pinfunction "1_1") (pintype "input"))
      (node (ref "U6") (pin "9") (pinfunction "VDPM_9") (pintype "input"))
    )
    (net (code "45") (name "Net-(U6-VTSB)") (class "Default")
      (node (ref "R12") (pin "2") (pinfunction "2_2") (pintype "input"))
      (node (ref "U6") (pin "4") (pinfunction "VTSB_4") (pintype "input"))
    )
    (net (code "46") (name "Net-(U7-ISET)") (class "Default")
      (node (ref "R13") (pin "2") (pinfunction "2_2") (pintype "unspecified"))
      (node (ref "U7") (pin "2") (pinfunction "ISET_2") (pintype "input"))
    )
    (net (code "47") (name "Net-(U7-PG#)") (class "Default")
      (node (ref "R20") (pin "2") (pinfunction "2_2") (pintype "input"))
      (node (ref "U7") (pin "6") (pinfunction "PG#_6") (pintype "input"))
    )
    (net (code "48") (name "Net-(U7-VDPM)") (class "Default")
      (node (ref "P18") (pin "1") (pinfunction "1_1") (pintype "input"))
      (node (ref "U7") (pin "9") (pinfunction "VDPM_9") (pintype "input"))
    )
    (net (code "49") (name "Net-(U7-VTSB)") (class "Default")
      (node (ref "R14") (pin "2") (pinfunction "2_2") (pintype "input"))
      (node (ref "U7") (pin "4") (pinfunction "VTSB_4") (pintype "input"))
    )
    (net (code "50") (name "Net-(USB1-CC1)") (class "Default")
      (node (ref "R1") (pin "2") (pinfunction "2_2") (pintype "input"))
      (node (ref "USB1") (pin "A5") (pinfunction "CC1_A5") (pintype "input"))
    )
    (net (code "51") (name "Net-(USB1-CC2)") (class "Default")
      (node (ref "R3") (pin "1") (pinfunction "1_1") (pintype "input"))
      (node (ref "USB1") (pin "B5") (pinfunction "CC2_B5") (pintype "input"))
    )
  )
)
